# 01_MAIN.net
KiCad netlist of a schematic drawn in Altium Designer
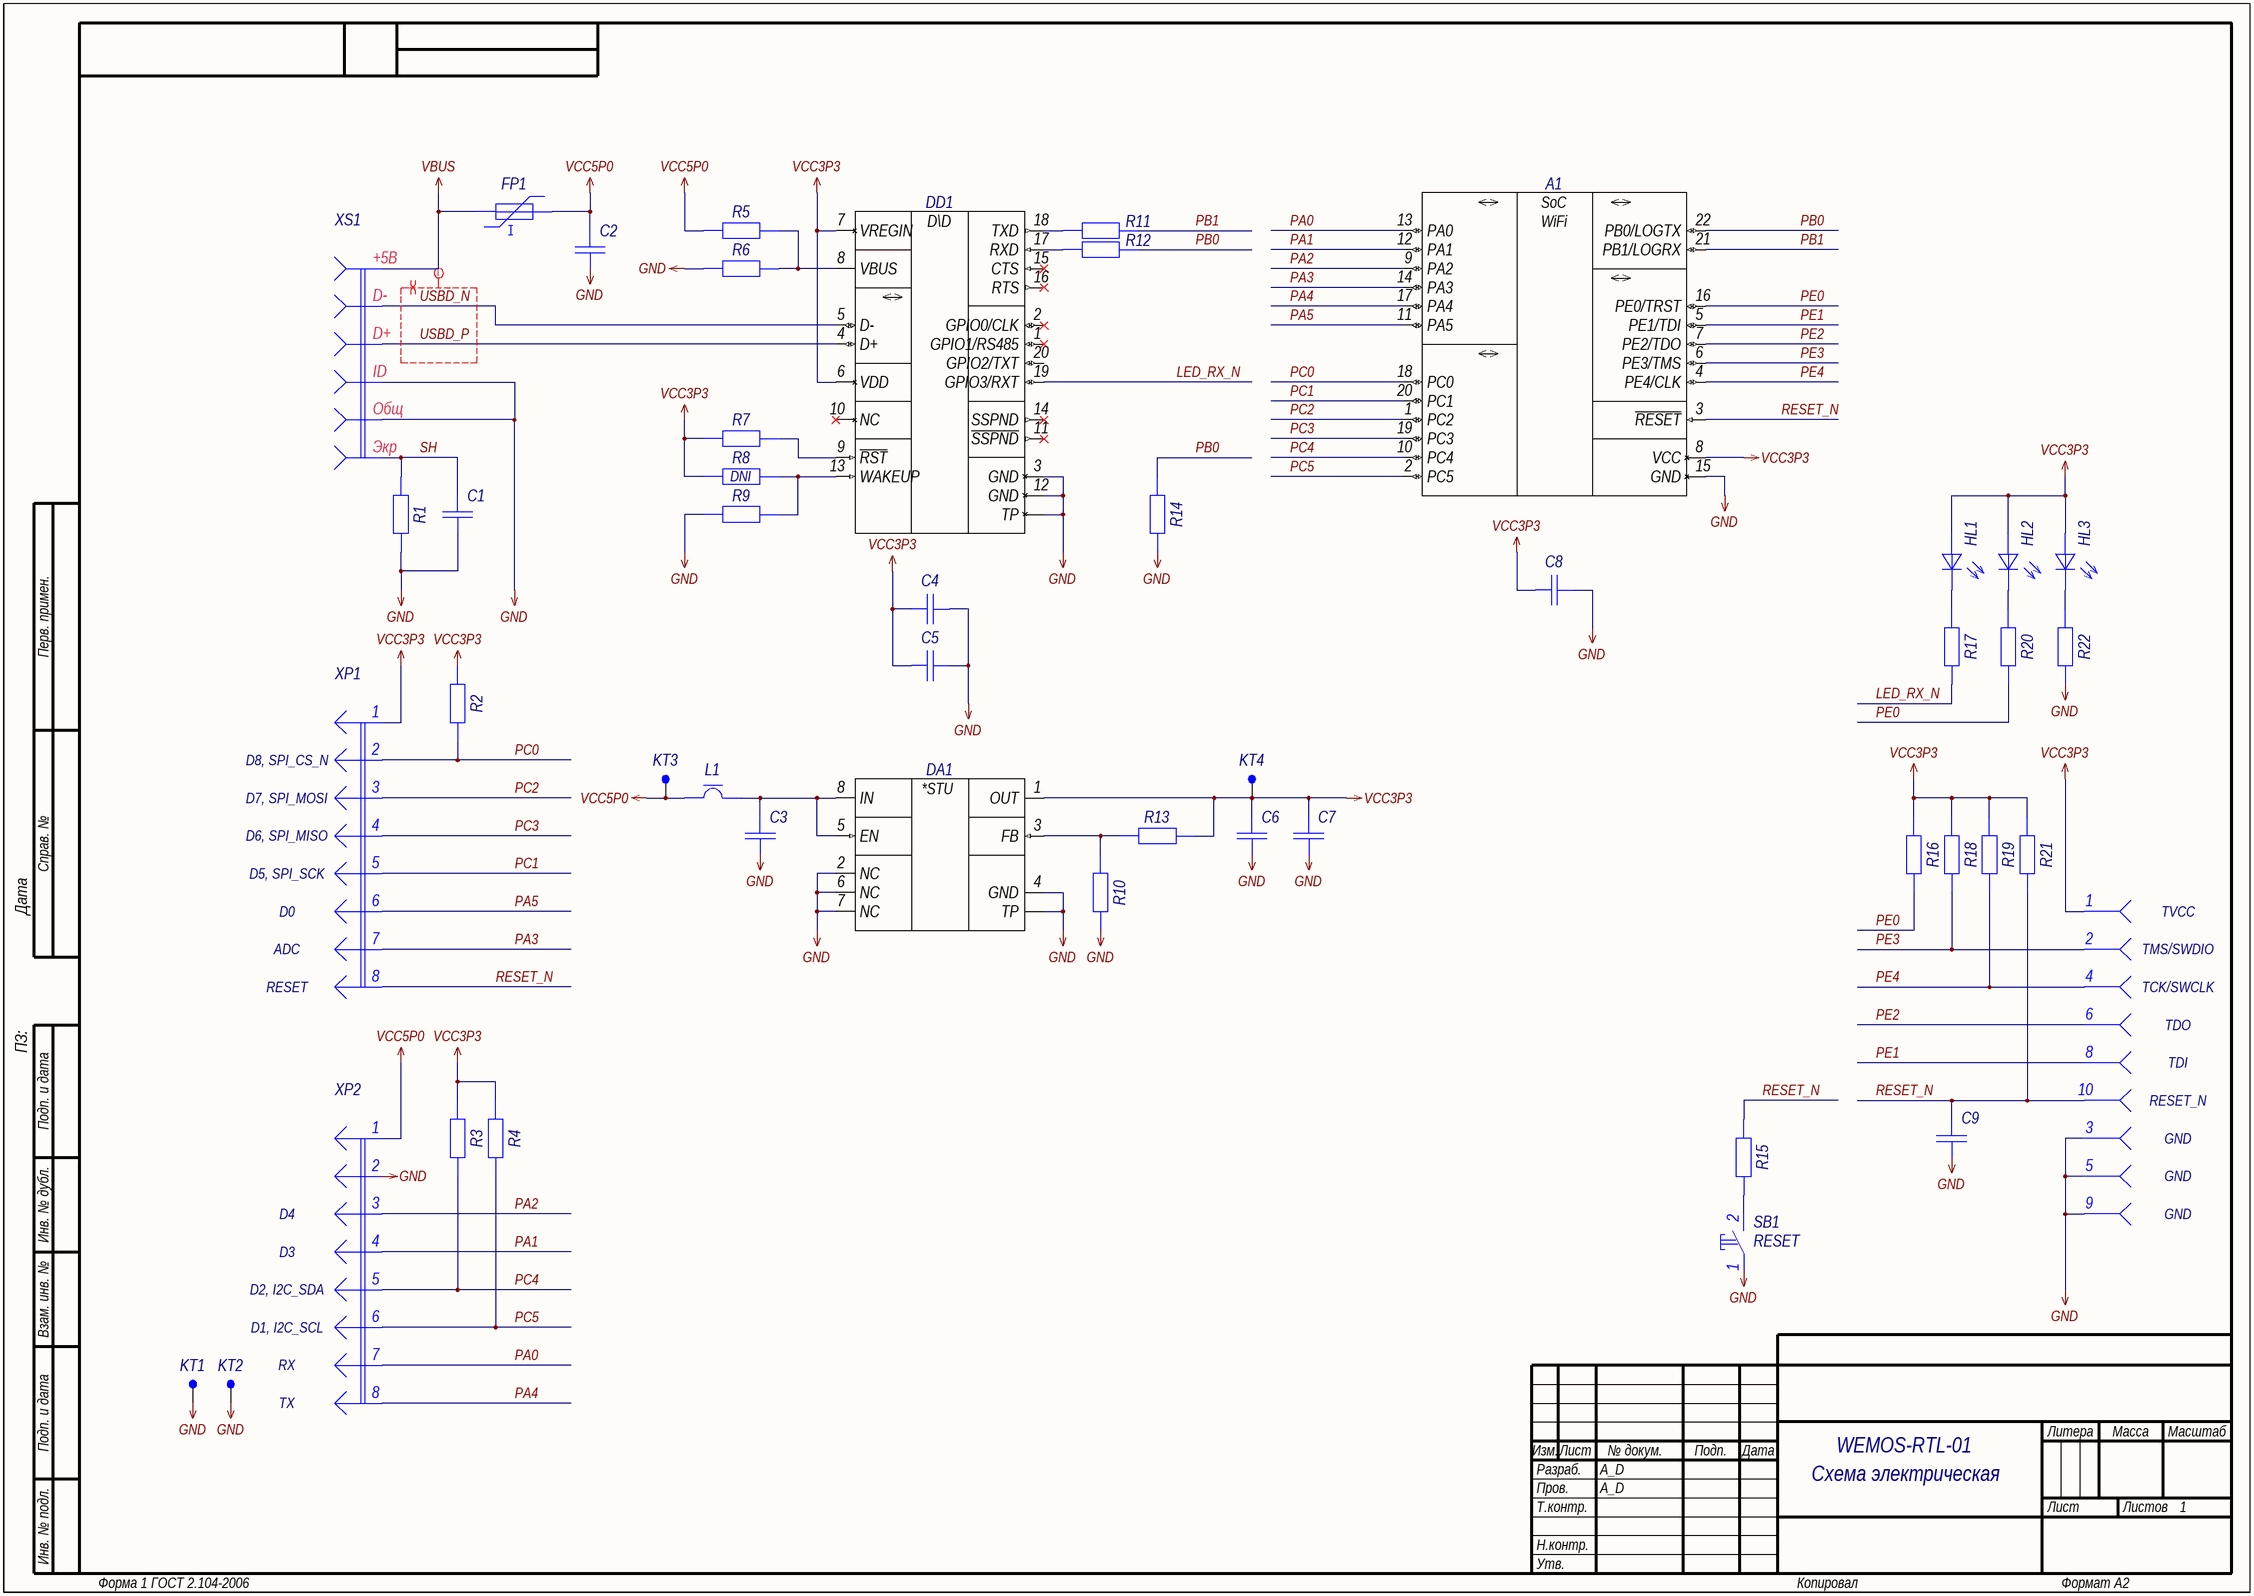
[diagram p0: 01_MAIN.SchDoc]

(export (version "E")
  (design (tool "Eeschema 10.0.6"))
  (components
    (comp (ref "A1")
      (value "RTL-00_01")
      (footprint "RTL-00")
      (fields
        (field (name "PART NUMBER") "RTL-00")
        (field (name "MANUFACTURER") "B&T")
        (field (name "PUBLISHER") "Andrew Danich")
      )
      (libsource (lib "ADLib") (part "RTL-00_01"))
    )
    (comp (ref "C1")
      (value "Capacitor")
      (footprint "C0603_L")
      (fields
        (field (name "PART NUMBER") "GRM188R72A104KA35D")
        (field (name "VOLTAGE") "100V")
        (field (name "TOLERANCE") "±10%")
        (field (name "PUBLISHER") "Andrew Danich")
      )
      (libsource (lib "ADLib") (part "Capacitor"))
    )
    (comp (ref "C2")
      (value "Capacitor")
      (footprint "C0603_L")
      (fields
        (field (name "PART NUMBER") "GRM188R60J106ME47D")
        (field (name "VOLTAGE") "6.3V")
        (field (name "TOLERANCE") "±20%")
        (field (name "PUBLISHER") "Andrew Danich")
      )
      (libsource (lib "ADLib") (part "Capacitor"))
    )
    (comp (ref "C3")
      (value "Capacitor")
      (footprint "C0402_L")
      (fields
        (field (name "PART NUMBER") "GRM155R60J475ME87D")
        (field (name "VOLTAGE") "6.3V")
        (field (name "TOLERANCE") "±20%")
        (field (name "PUBLISHER") "Andrew Danich")
      )
      (libsource (lib "ADLib") (part "Capacitor"))
    )
    (comp (ref "C4")
      (value "Capacitor")
      (footprint "C0402_L")
      (fields
        (field (name "PART NUMBER") "GRM155R60J475ME87D")
        (field (name "VOLTAGE") "6.3V")
        (field (name "TOLERANCE") "±20%")
        (field (name "PUBLISHER") "Andrew Danich")
      )
      (libsource (lib "ADLib") (part "Capacitor"))
    )
    (comp (ref "C5")
      (value "Capacitor")
      (footprint "C0402_L")
      (fields
        (field (name "PART NUMBER") "GCM155R71C104KA55D")
        (field (name "VOLTAGE") "16V")
        (field (name "TOLERANCE") "±10%")
        (field (name "PUBLISHER") "Andrew Danich")
      )
      (libsource (lib "ADLib") (part "Capacitor"))
    )
    (comp (ref "C6")
      (value "Capacitor")
      (footprint "C0402_L")
      (fields
        (field (name "PART NUMBER") "GRM155R60J475ME87D")
        (field (name "VOLTAGE") "6.3V")
        (field (name "TOLERANCE") "±20%")
        (field (name "PUBLISHER") "Andrew Danich")
      )
      (libsource (lib "ADLib") (part "Capacitor"))
    )
    (comp (ref "C7")
      (value "Capacitor")
      (footprint "C0402_L")
      (fields
        (field (name "PART NUMBER") "GRM155R60J475ME87D")
        (field (name "VOLTAGE") "6.3V")
        (field (name "TOLERANCE") "±20%")
        (field (name "PUBLISHER") "Andrew Danich")
      )
      (libsource (lib "ADLib") (part "Capacitor"))
    )
    (comp (ref "C8")
      (value "Capacitor")
      (footprint "C0402_L")
      (fields
        (field (name "PART NUMBER") "GRM155R60J475ME87D")
        (field (name "VOLTAGE") "6.3V")
        (field (name "TOLERANCE") "±20%")
        (field (name "PUBLISHER") "Andrew Danich")
      )
      (libsource (lib "ADLib") (part "Capacitor"))
    )
    (comp (ref "C9")
      (value "Capacitor")
      (footprint "C0402_L")
      (fields
        (field (name "PART NUMBER") "GCM155R71C104KA55D")
        (field (name "VOLTAGE") "16V")
        (field (name "TOLERANCE") "±10%")
        (field (name "PUBLISHER") "Andrew Danich")
      )
      (libsource (lib "ADLib") (part "Capacitor"))
    )
    (comp (ref "DA1")
      (value "TPS73701DRB")
      (footprint "VSON-8_065P300X300X100_N")
      (fields
        (field (name "PART NUMBER") "TPS73701DRBR")
        (field (name "MANUFACTURER") "Texas Instruments")
        (field (name "PUBLISHER") "Andrew Danich")
      )
      (libsource (lib "ADLib") (part "TPS73701DRB"))
    )
    (comp (ref "DD1")
      (value "CP2102N-xxx-GQFN20")
      (footprint "QFN-20_050P300X300X080_N")
      (fields
        (field (name "PART NUMBER") "CP2102N-A01-GQFN20")
        (field (name "MANUFACTURER") "Silicon Labs")
        (field (name "PUBLISHER") "Andrew Danich")
      )
      (libsource (lib "ADLib") (part "CP2102N-xxx-GQFN20"))
    )
    (comp (ref "FP1")
      (value "Fuse_PTC")
      (footprint "F0603_L_H075")
      (fields (field (name "PART NUMBER") "0603L100SLYR") (field (name "MANUFACTURER") "Littelfuse"))
      (libsource (lib "ADLib") (part "Fuse_PTC"))
    )
    (comp (ref "HL1")
      (value "RX")
      (footprint "LD0402_L")
      (fields
        (field (name "PART NUMBER") "KPHHS-1005SURCK")
        (field (name "MANUFACTURER") "Kingbright")
        (field (name "PUBLISHER") "Andrew Danich")
      )
      (libsource (lib "ADLib") (part "Led-1"))
    )
    (comp (ref "HL2")
      (value "USER")
      (footprint "LD0402_L")
      (fields
        (field (name "PART NUMBER") "KPHHS-1005QBC-D-V")
        (field (name "MANUFACTURER") "Kingbright")
        (field (name "PUBLISHER") "Andrew Danich")
      )
      (libsource (lib "ADLib") (part "Led-1"))
    )
    (comp (ref "HL3")
      (value "POWER")
      (footprint "LD0402_L")
      (fields
        (field (name "PART NUMBER") "KPHHS-1005CGCK")
        (field (name "MANUFACTURER") "Kingbright")
        (field (name "PUBLISHER") "Andrew Danich")
      )
      (libsource (lib "ADLib") (part "Led-1"))
    )
    (comp (ref "KT1")
      (value "GND")
      (footprint "TP-SMT-R-0.8mm")
      (fields (field (name "PART NUMBER") "TestPoint-SMT-GND") (field (name "PUBLISHER") "Andrew Danich"))
      (libsource (lib "ADLib") (part "TP-S-1"))
    )
    (comp (ref "KT2")
      (value "GND")
      (footprint "TP-SMT-R-0.8mm")
      (fields (field (name "PART NUMBER") "TestPoint-SMT-GND") (field (name "PUBLISHER") "Andrew Danich"))
      (libsource (lib "ADLib") (part "TP-S-1"))
    )
    (comp (ref "KT3")
      (value "5P0")
      (footprint "TP-SMT-C-0.5mm")
      (fields (field (name "PART NUMBER") "TestPoint-SMT") (field (name "PUBLISHER") "Andrew Danich"))
      (libsource (lib "ADLib") (part "TP-S-1"))
    )
    (comp (ref "KT4")
      (value "3P3")
      (footprint "TP-SMT-C-0.5mm")
      (fields (field (name "PART NUMBER") "TestPoint-SMT") (field (name "PUBLISHER") "Andrew Danich"))
      (libsource (lib "ADLib") (part "TP-S-1"))
    )
    (comp (ref "L1")
      (value "FerriteBead")
      (footprint "L0402_L")
      (fields
        (field (name "PART NUMBER") "BLM15PD121SN1D")
        (field (name "TOLERANCE") "±25%")
        (field (name "MANUFACTURER") "Murata")
        (field (name "PUBLISHER") "Andrew Danich")
      )
      (libsource (lib "ADLib") (part "FerriteBead"))
    )
    (comp (ref "R1")
      (value "Resistor")
      (footprint "R0603_L")
      (fields
        (field (name "PART NUMBER") "RC0603JR-070R")
        (field (name "TOLERANCE") "±5%")
        (field (name "MANUFACTURER") "Yageo")
        (field (name "PUBLISHER") "Andrew Danich")
      )
      (libsource (lib "ADLib") (part "Resistor"))
    )
    (comp (ref "R2")
      (value "Resistor")
      (footprint "R0402_L")
      (fields
        (field (name "PART NUMBER") "RC0402JR-0710KL")
        (field (name "TOLERANCE") "±5%")
        (field (name "MANUFACTURER") "Yageo")
        (field (name "PUBLISHER") "Andrew Danich")
      )
      (libsource (lib "ADLib") (part "Resistor"))
    )
    (comp (ref "R3")
      (value "Resistor")
      (footprint "R0402_L")
      (fields
        (field (name "PART NUMBER") "RC0402JR-0710KL")
        (field (name "TOLERANCE") "±5%")
        (field (name "MANUFACTURER") "Yageo")
        (field (name "PUBLISHER") "Andrew Danich")
      )
      (libsource (lib "ADLib") (part "Resistor"))
    )
    (comp (ref "R4")
      (value "Resistor")
      (footprint "R0402_L")
      (fields
        (field (name "PART NUMBER") "RC0402JR-0710KL")
        (field (name "TOLERANCE") "±5%")
        (field (name "MANUFACTURER") "Yageo")
        (field (name "PUBLISHER") "Andrew Danich")
      )
      (libsource (lib "ADLib") (part "Resistor"))
    )
    (comp (ref "R5")
      (value "Resistor")
      (footprint "R0402_L")
      (fields
        (field (name "PART NUMBER") "RC0402FR-0722K1L")
        (field (name "TOLERANCE") "±1%")
        (field (name "MANUFACTURER") "Yageo")
        (field (name "PUBLISHER") "Andrew Danich")
      )
      (libsource (lib "ADLib") (part "Resistor"))
    )
    (comp (ref "R6")
      (value "Resistor")
      (footprint "R0402_L")
      (fields
        (field (name "PART NUMBER") "RC0402FR-0747KL")
        (field (name "TOLERANCE") "±1%")
        (field (name "MANUFACTURER") "Yageo")
        (field (name "PUBLISHER") "Andrew Danich")
      )
      (libsource (lib "ADLib") (part "Resistor"))
    )
    (comp (ref "R7")
      (value "Resistor")
      (footprint "R0402_L")
      (fields
        (field (name "PART NUMBER") "RC0402JR-0710KL")
        (field (name "TOLERANCE") "±5%")
        (field (name "MANUFACTURER") "Yageo")
        (field (name "PUBLISHER") "Andrew Danich")
      )
      (libsource (lib "ADLib") (part "Resistor"))
    )
    (comp (ref "R8")
      (value "Resistor")
      (footprint "R0402_L")
      (fields
        (field (name "PART NUMBER") "RC0402JR-0710KL")
        (field (name "TOLERANCE") "±5%")
        (field (name "MANUFACTURER") "Yageo")
        (field (name "PUBLISHER") "Andrew Danich")
      )
      (libsource (lib "ADLib") (part "Resistor"))
    )
    (comp (ref "R9")
      (value "Resistor")
      (footprint "R0402_L")
      (fields
        (field (name "PART NUMBER") "RC0402JR-070RL")
        (field (name "TOLERANCE") "±5%")
        (field (name "MANUFACTURER") "Yageo")
        (field (name "PUBLISHER") "Andrew Danich")
      )
      (libsource (lib "ADLib") (part "Resistor"))
    )
    (comp (ref "R10")
      (value "Resistor")
      (footprint "R0402_L")
      (fields
        (field (name "PART NUMBER") "RC0402FR-0712KL")
        (field (name "TOLERANCE") "±1%")
        (field (name "MANUFACTURER") "Yageo")
        (field (name "PUBLISHER") "Andrew Danich")
      )
      (libsource (lib "ADLib") (part "Resistor"))
    )
    (comp (ref "R11")
      (value "Resistor")
      (footprint "R0402_L")
      (fields
        (field (name "PART NUMBER") "RC0402JR-070RL")
        (field (name "TOLERANCE") "±5%")
        (field (name "MANUFACTURER") "Yageo")
        (field (name "PUBLISHER") "Andrew Danich")
      )
      (libsource (lib "ADLib") (part "Resistor"))
    )
    (comp (ref "R12")
      (value "Resistor")
      (footprint "R0402_L")
      (fields
        (field (name "PART NUMBER") "RC0402JR-070RL")
        (field (name "TOLERANCE") "±5%")
        (field (name "MANUFACTURER") "Yageo")
        (field (name "PUBLISHER") "Andrew Danich")
      )
      (libsource (lib "ADLib") (part "Resistor"))
    )
    (comp (ref "R13")
      (value "Resistor")
      (footprint "R0402_L")
      (fields
        (field (name "PART NUMBER") "RC0402FR-0722K1L")
        (field (name "TOLERANCE") "±1%")
        (field (name "MANUFACTURER") "Yageo")
        (field (name "PUBLISHER") "Andrew Danich")
      )
      (libsource (lib "ADLib") (part "Resistor"))
    )
    (comp (ref "R14")
      (value "Resistor")
      (footprint "R0402_L")
      (fields
        (field (name "PART NUMBER") "RC0402JR-0710KL")
        (field (name "TOLERANCE") "±5%")
        (field (name "MANUFACTURER") "Yageo")
        (field (name "PUBLISHER") "Andrew Danich")
      )
      (libsource (lib "ADLib") (part "Resistor"))
    )
    (comp (ref "R15")
      (value "Resistor")
      (footprint "R0402_L")
      (fields
        (field (name "PART NUMBER") "RC0402JR-0720RL")
        (field (name "TOLERANCE") "±5%")
        (field (name "MANUFACTURER") "Yageo")
        (field (name "PUBLISHER") "Andrew Danich")
      )
      (libsource (lib "ADLib") (part "Resistor"))
    )
    (comp (ref "R16")
      (value "Resistor")
      (footprint "R0402_L")
      (fields
        (field (name "PART NUMBER") "RC0402JR-0710KL")
        (field (name "TOLERANCE") "±5%")
        (field (name "MANUFACTURER") "Yageo")
        (field (name "PUBLISHER") "Andrew Danich")
      )
      (libsource (lib "ADLib") (part "Resistor"))
    )
    (comp (ref "R17")
      (value "Resistor")
      (footprint "R0402_L")
      (fields
        (field (name "PART NUMBER") "RC0402JR-071KL")
        (field (name "TOLERANCE") "±5%")
        (field (name "MANUFACTURER") "Yageo")
        (field (name "PUBLISHER") "Andrew Danich")
      )
      (libsource (lib "ADLib") (part "Resistor"))
    )
    (comp (ref "R18")
      (value "Resistor")
      (footprint "R0402_L")
      (fields
        (field (name "PART NUMBER") "RC0402JR-0710KL")
        (field (name "TOLERANCE") "±5%")
        (field (name "MANUFACTURER") "Yageo")
        (field (name "PUBLISHER") "Andrew Danich")
      )
      (libsource (lib "ADLib") (part "Resistor"))
    )
    (comp (ref "R19")
      (value "Resistor")
      (footprint "R0402_L")
      (fields
        (field (name "PART NUMBER") "RC0402JR-0710KL")
        (field (name "TOLERANCE") "±5%")
        (field (name "MANUFACTURER") "Yageo")
        (field (name "PUBLISHER") "Andrew Danich")
      )
      (libsource (lib "ADLib") (part "Resistor"))
    )
    (comp (ref "R20")
      (value "Resistor")
      (footprint "R0402_L")
      (fields
        (field (name "PART NUMBER") "RC0402JR-071KL")
        (field (name "TOLERANCE") "±5%")
        (field (name "MANUFACTURER") "Yageo")
        (field (name "PUBLISHER") "Andrew Danich")
      )
      (libsource (lib "ADLib") (part "Resistor"))
    )
    (comp (ref "R21")
      (value "Resistor")
      (footprint "R0402_L")
      (fields
        (field (name "PART NUMBER") "RC0402JR-0710KL")
        (field (name "TOLERANCE") "±5%")
        (field (name "MANUFACTURER") "Yageo")
        (field (name "PUBLISHER") "Andrew Danich")
      )
      (libsource (lib "ADLib") (part "Resistor"))
    )
    (comp (ref "R22")
      (value "Resistor")
      (footprint "R0402_L")
      (fields
        (field (name "PART NUMBER") "RC0402JR-071KL")
        (field (name "TOLERANCE") "±5%")
        (field (name "MANUFACTURER") "Yageo")
        (field (name "PUBLISHER") "Andrew Danich")
      )
      (libsource (lib "ADLib") (part "Resistor"))
    )
    (comp (ref "SB1")
      (value "RESET")
      (footprint "1TS003B-Series")
      (fields
        (field (name "PART NUMBER") "1TS003B-1600-3500A-CT")
        (field (name "MANUFACTURER") "Hongyuan Precision")
        (field (name "PUBLISHER") "Andrew Danich")
      )
      (libsource (lib "ADLib") (part "BT-01x-01p"))
    )
    (comp (ref "XP1")
      (value "Text")
      (footprint "PLS-8")
      (fields (field (name "PART NUMBER") "PLS-8") (field (name "PUBLISHER") "Andrew Danich"))
      (libsource (lib "ADLib") (part "Con-8-M"))
    )
    (comp (ref "XP2")
      (value "Text")
      (footprint "PLS-8")
      (fields (field (name "PART NUMBER") "PLS-8") (field (name "PUBLISHER") "Andrew Danich"))
      (libsource (lib "ADLib") (part "Con-8-M"))
    )
    (comp (ref "XS1")
      (value "Text")
      (footprint "1981568-1")
      (fields
        (field (name "PART NUMBER") "1981568-1")
        (field (name "MANUFACTURER") "TE Connectivity")
        (field (name "PUBLISHER") "Andrew Danich")
      )
      (libsource (lib "ADLib") (part "Con-6-F-USB"))
    )
    (comp (ref "XS2")
      (value "JTAG")
      (footprint "XF2M-1015-1A")
      (fields
        (field (name "PART NUMBER") "XF2M-1015-1A")
        (field (name "MANUFACTURER") "Omron Electronics")
        (field (name "PUBLISHER") "Viktor Klishin")
      )
      (libsource (lib "ADLib") (part "Con-10-F_S"))
    )
  )
  (nets
    (net (code "1") (name "/LED_RX_N") (class "Default")
      (node (ref "DD1") (pin "19") (pinfunction "GPIO3/RXT_19") (pintype "bidirectional"))
      (node (ref "R17") (pin "1") (pinfunction "1_1") (pintype "passive"))
    )
    (net (code "2") (name "/PA0") (class "Default")
      (node (ref "A1") (pin "13") (pinfunction "PA0_13") (pintype "bidirectional"))
      (node (ref "XP2") (pin "7") (pintype "passive"))
    )
    (net (code "3") (name "/PA1") (class "Default")
      (node (ref "A1") (pin "12") (pinfunction "PA1_12") (pintype "bidirectional"))
      (node (ref "XP2") (pin "4") (pintype "passive"))
    )
    (net (code "4") (name "/PA2") (class "Default")
      (node (ref "A1") (pin "9") (pinfunction "PA2_9") (pintype "bidirectional"))
      (node (ref "XP2") (pin "3") (pintype "passive"))
    )
    (net (code "5") (name "/PA3") (class "Default")
      (node (ref "A1") (pin "14") (pinfunction "PA3_14") (pintype "bidirectional"))
      (node (ref "XP1") (pin "7") (pintype "passive"))
    )
    (net (code "6") (name "/PA4") (class "Default")
      (node (ref "A1") (pin "17") (pinfunction "PA4_17") (pintype "bidirectional"))
      (node (ref "XP2") (pin "8") (pintype "passive"))
    )
    (net (code "7") (name "/PA5") (class "Default")
      (node (ref "A1") (pin "11") (pinfunction "PA5_11") (pintype "bidirectional"))
      (node (ref "XP1") (pin "6") (pintype "passive"))
    )
    (net (code "8") (name "/PB0") (class "Default")
      (node (ref "A1") (pin "22") (pinfunction "PB0/LOGTX_22") (pintype "bidirectional"))
      (node (ref "R12") (pin "2") (pinfunction "2_2") (pintype "passive"))
      (node (ref "R14") (pin "2") (pinfunction "2_2") (pintype "passive"))
    )
    (net (code "9") (name "/PB1") (class "Default")
      (node (ref "A1") (pin "21") (pinfunction "PB1/LOGRX_21") (pintype "bidirectional"))
      (node (ref "R11") (pin "2") (pinfunction "2_2") (pintype "passive"))
    )
    (net (code "10") (name "/PC0") (class "Default")
      (node (ref "A1") (pin "18") (pinfunction "PC0_18") (pintype "bidirectional"))
      (node (ref "R2") (pin "2") (pinfunction "2_2") (pintype "passive"))
      (node (ref "XP1") (pin "2") (pintype "passive"))
    )
    (net (code "11") (name "/PC1") (class "Default")
      (node (ref "A1") (pin "20") (pinfunction "PC1_20") (pintype "bidirectional"))
      (node (ref "XP1") (pin "5") (pintype "passive"))
    )
    (net (code "12") (name "/PC2") (class "Default")
      (node (ref "A1") (pin "1") (pinfunction "PC2_1") (pintype "bidirectional"))
      (node (ref "XP1") (pin "3") (pintype "passive"))
    )
    (net (code "13") (name "/PC3") (class "Default")
      (node (ref "A1") (pin "19") (pinfunction "PC3_19") (pintype "bidirectional"))
      (node (ref "XP1") (pin "4") (pintype "passive"))
    )
    (net (code "14") (name "/PC4") (class "Default")
      (node (ref "A1") (pin "10") (pinfunction "PC4_10") (pintype "bidirectional"))
      (node (ref "R3") (pin "2") (pinfunction "2_2") (pintype "passive"))
      (node (ref "XP2") (pin "5") (pintype "passive"))
    )
    (net (code "15") (name "/PC5") (class "Default")
      (node (ref "A1") (pin "2") (pinfunction "PC5_2") (pintype "bidirectional"))
      (node (ref "R4") (pin "2") (pinfunction "2_2") (pintype "passive"))
      (node (ref "XP2") (pin "6") (pintype "passive"))
    )
    (net (code "16") (name "/PE0") (class "Default")
      (node (ref "A1") (pin "16") (pinfunction "PE0/TRST_16") (pintype "bidirectional"))
      (node (ref "R16") (pin "2") (pinfunction "2_2") (pintype "passive"))
      (node (ref "R20") (pin "1") (pinfunction "1_1") (pintype "passive"))
    )
    (net (code "17") (name "/PE1") (class "Default")
      (node (ref "A1") (pin "5") (pinfunction "PE1/TDI_5") (pintype "bidirectional"))
      (node (ref "XS2") (pin "8") (pintype "passive"))
    )
    (net (code "18") (name "/PE2") (class "Default")
      (node (ref "A1") (pin "7") (pinfunction "PE2/TDO_7") (pintype "bidirectional"))
      (node (ref "XS2") (pin "6") (pintype "passive"))
    )
    (net (code "19") (name "/PE3") (class "Default")
      (node (ref "A1") (pin "6") (pinfunction "PE3/TMS_6") (pintype "bidirectional"))
      (node (ref "R18") (pin "2") (pinfunction "2_2") (pintype "passive"))
      (node (ref "XS2") (pin "2") (pintype "passive"))
    )
    (net (code "20") (name "/PE4") (class "Default")
      (node (ref "A1") (pin "4") (pinfunction "PE4/CLK_4") (pintype "bidirectional"))
      (node (ref "R19") (pin "2") (pinfunction "2_2") (pintype "passive"))
      (node (ref "XS2") (pin "4") (pintype "passive"))
    )
    (net (code "21") (name "/RESET_N") (class "Default")
      (node (ref "A1") (pin "3") (pinfunction "~{RESET}_3") (pintype "input"))
      (node (ref "C9") (pin "2") (pinfunction "2_2") (pintype "passive"))
      (node (ref "R15") (pin "2") (pinfunction "2_2") (pintype "passive"))
      (node (ref "R21") (pin "2") (pinfunction "2_2") (pintype "passive"))
      (node (ref "XP1") (pin "8") (pintype "passive"))
      (node (ref "XS2") (pin "10") (pintype "passive"))
    )
    (net (code "22") (name "/SH") (class "Default")
      (node (ref "C1") (pin "2") (pinfunction "2_2") (pintype "passive"))
      (node (ref "R1") (pin "2") (pinfunction "2_2") (pintype "passive"))
      (node (ref "XS1") (pin "6") (pintype "passive"))
    )
    (net (code "23") (name "/USBD_N") (class "Default")
      (node (ref "DD1") (pin "5") (pinfunction "D-_5") (pintype "bidirectional"))
      (node (ref "XS1") (pin "2") (pintype "passive"))
    )
    (net (code "24") (name "/USBD_P") (class "Default")
      (node (ref "DD1") (pin "4") (pinfunction "D+_4") (pintype "bidirectional"))
      (node (ref "XS1") (pin "3") (pintype "passive"))
    )
    (net (code "25") (name "GND") (class "Default")
      (node (ref "A1") (pin "15") (pinfunction "GND_15") (pintype "power_in"))
      (node (ref "C1") (pin "1") (pinfunction "1_1") (pintype "passive"))
      (node (ref "C2") (pin "1") (pinfunction "1_1") (pintype "passive"))
      (node (ref "C3") (pin "1") (pinfunction "1_1") (pintype "passive"))
      (node (ref "C4") (pin "1") (pinfunction "1_1") (pintype "passive"))
      (node (ref "C5") (pin "1") (pinfunction "1_1") (pintype "passive"))
      (node (ref "C6") (pin "1") (pinfunction "1_1") (pintype "passive"))
      (node (ref "C7") (pin "1") (pinfunction "1_1") (pintype "passive"))
      (node (ref "C8") (pin "1") (pinfunction "1_1") (pintype "passive"))
      (node (ref "C9") (pin "1") (pinfunction "1_1") (pintype "passive"))
      (node (ref "DA1") (pin "2") (pinfunction "NC_2") (pintype "passive"))
      (node (ref "DA1") (pin "4") (pinfunction "GND_4") (pintype "power_in"))
      (node (ref "DA1") (pin "6") (pinfunction "NC_6") (pintype "passive"))
      (node (ref "DA1") (pin "7") (pinfunction "NC_7") (pintype "passive"))
      (node (ref "DA1") (pin "TP") (pinfunction "TP_TP") (pintype "passive"))
      (node (ref "DD1") (pin "12") (pinfunction "GND_12") (pintype "power_in"))
      (node (ref "DD1") (pin "3") (pinfunction "GND_3") (pintype "power_in"))
      (node (ref "DD1") (pin "TP") (pinfunction "TP_TP") (pintype "power_in"))
      (node (ref "KT1") (pin "1") (pinfunction "1_1") (pintype "passive"))
      (node (ref "KT2") (pin "1") (pinfunction "1_1") (pintype "passive"))
      (node (ref "R1") (pin "1") (pinfunction "1_1") (pintype "passive"))
      (node (ref "R10") (pin "1") (pinfunction "1_1") (pintype "passive"))
      (node (ref "R14") (pin "1") (pinfunction "1_1") (pintype "passive"))
      (node (ref "R22") (pin "1") (pinfunction "1_1") (pintype "passive"))
      (node (ref "R6") (pin "1") (pinfunction "1_1") (pintype "passive"))
      (node (ref "R9") (pin "1") (pinfunction "1_1") (pintype "passive"))
      (node (ref "SB1") (pin "1") (pintype "passive"))
      (node (ref "XP2") (pin "2") (pintype "passive"))
      (node (ref "XS1") (pin "4") (pintype "passive"))
      (node (ref "XS1") (pin "5") (pintype "passive"))
      (node (ref "XS2") (pin "3") (pintype "passive"))
      (node (ref "XS2") (pin "5") (pintype "passive"))
      (node (ref "XS2") (pin "9") (pintype "passive"))
    )
    (net (code "26") (name "Net-(DA1-EN)") (class "Default")
      (node (ref "C3") (pin "2") (pinfunction "2_2") (pintype "passive"))
      (node (ref "DA1") (pin "5") (pinfunction "EN_5") (pintype "input"))
      (node (ref "DA1") (pin "8") (pinfunction "IN_8") (pintype "power_in"))
      (node (ref "L1") (pin "2") (pinfunction "2_2") (pintype "passive"))
    )
    (net (code "27") (name "Net-(DA1-FB)") (class "Default")
      (node (ref "DA1") (pin "3") (pinfunction "FB_3") (pintype "input"))
      (node (ref "R10") (pin "2") (pinfunction "2_2") (pintype "passive"))
      (node (ref "R13") (pin "1") (pinfunction "1_1") (pintype "passive"))
    )
    (net (code "28") (name "Net-(DD1-RXD)") (class "Default")
      (node (ref "DD1") (pin "17") (pinfunction "RXD_17") (pintype "input"))
      (node (ref "R12") (pin "1") (pinfunction "1_1") (pintype "passive"))
    )
    (net (code "29") (name "Net-(DD1-TXD)") (class "Default")
      (node (ref "DD1") (pin "18") (pinfunction "TXD_18") (pintype "output"))
      (node (ref "R11") (pin "1") (pinfunction "1_1") (pintype "passive"))
    )
    (net (code "30") (name "Net-(DD1-VBUS)") (class "Default")
      (node (ref "DD1") (pin "8") (pinfunction "VBUS_8") (pintype "power_in"))
      (node (ref "R5") (pin "2") (pinfunction "2_2") (pintype "passive"))
      (node (ref "R6") (pin "2") (pinfunction "2_2") (pintype "passive"))
    )
    (net (code "31") (name "Net-(DD1-WAKEUP)") (class "Default")
      (node (ref "DD1") (pin "13") (pinfunction "WAKEUP_13") (pintype "input"))
      (node (ref "R8") (pin "1") (pinfunction "1_1") (pintype "passive"))
      (node (ref "R9") (pin "2") (pinfunction "2_2") (pintype "passive"))
    )
    (net (code "32") (name "Net-(DD1-~{RST})") (class "Default")
      (node (ref "DD1") (pin "9") (pinfunction "~{RST}_9") (pintype "input"))
      (node (ref "R7") (pin "1") (pinfunction "1_1") (pintype "passive"))
    )
    (net (code "33") (name "Net-(HL1-К)") (class "Default")
      (node (ref "HL1") (pin "2") (pinfunction "К_2") (pintype "passive"))
      (node (ref "R17") (pin "2") (pinfunction "2_2") (pintype "passive"))
    )
    (net (code "34") (name "Net-(HL2-К)") (class "Default")
      (node (ref "HL2") (pin "2") (pinfunction "К_2") (pintype "passive"))
      (node (ref "R20") (pin "2") (pinfunction "2_2") (pintype "passive"))
    )
    (net (code "35") (name "Net-(HL3-К)") (class "Default")
      (node (ref "HL3") (pin "2") (pinfunction "К_2") (pintype "passive"))
      (node (ref "R22") (pin "2") (pinfunction "2_2") (pintype "passive"))
    )
    (net (code "36") (name "Net-(R15-Pad1)") (class "Default")
      (node (ref "R15") (pin "1") (pinfunction "1_1") (pintype "passive"))
      (node (ref "SB1") (pin "2") (pintype "passive"))
    )
    (net (code "37") (name "VBUS") (class "Default")
      (node (ref "FP1") (pin "1") (pinfunction "1_1") (pintype "passive"))
      (node (ref "XS1") (pin "1") (pintype "passive"))
    )
    (net (code "38") (name "VCC3P3") (class "Default")
      (node (ref "A1") (pin "8") (pinfunction "VCC_8") (pintype "power_in"))
      (node (ref "C4") (pin "2") (pinfunction "2_2") (pintype "passive"))
      (node (ref "C5") (pin "2") (pinfunction "2_2") (pintype "passive"))
      (node (ref "C6") (pin "2") (pinfunction "2_2") (pintype "passive"))
      (node (ref "C7") (pin "2") (pinfunction "2_2") (pintype "passive"))
      (node (ref "C8") (pin "2") (pinfunction "2_2") (pintype "passive"))
      (node (ref "DA1") (pin "1") (pinfunction "OUT_1") (pintype "power_in"))
      (node (ref "DD1") (pin "6") (pinfunction "VDD_6") (pintype "power_in"))
      (node (ref "DD1") (pin "7") (pinfunction "VREGIN_7") (pintype "power_in"))
      (node (ref "HL1") (pin "1") (pinfunction "А_1") (pintype "passive"))
      (node (ref "HL2") (pin "1") (pinfunction "А_1") (pintype "passive"))
      (node (ref "HL3") (pin "1") (pinfunction "А_1") (pintype "passive"))
      (node (ref "KT4") (pin "1") (pinfunction "1_1") (pintype "passive"))
      (node (ref "R13") (pin "2") (pinfunction "2_2") (pintype "passive"))
      (node (ref "R16") (pin "1") (pinfunction "1_1") (pintype "passive"))
      (node (ref "R18") (pin "1") (pinfunction "1_1") (pintype "passive"))
      (node (ref "R19") (pin "1") (pinfunction "1_1") (pintype "passive"))
      (node (ref "R2") (pin "1") (pinfunction "1_1") (pintype "passive"))
      (node (ref "R21") (pin "1") (pinfunction "1_1") (pintype "passive"))
      (node (ref "R3") (pin "1") (pinfunction "1_1") (pintype "passive"))
      (node (ref "R4") (pin "1") (pinfunction "1_1") (pintype "passive"))
      (node (ref "R7") (pin "2") (pinfunction "2_2") (pintype "passive"))
      (node (ref "R8") (pin "2") (pinfunction "2_2") (pintype "passive"))
      (node (ref "XP1") (pin "1") (pintype "passive"))
      (node (ref "XS2") (pin "1") (pintype "passive"))
    )
    (net (code "39") (name "VCC5P0") (class "Default")
      (node (ref "C2") (pin "2") (pinfunction "2_2") (pintype "passive"))
      (node (ref "FP1") (pin "2") (pinfunction "2_2") (pintype "passive"))
      (node (ref "KT3") (pin "1") (pinfunction "1_1") (pintype "passive"))
      (node (ref "L1") (pin "1") (pinfunction "1_1") (pintype "passive"))
      (node (ref "R5") (pin "1") (pinfunction "1_1") (pintype "passive"))
      (node (ref "XP2") (pin "1") (pintype "passive"))
    )
    (net (code "40") (name "unconnected-(DD1-CTS-Pad15)") (class "Default")
      (node (ref "DD1") (pin "15") (pinfunction "CTS_15") (pintype "input+no_connect"))
    )
    (net (code "41") (name "unconnected-(DD1-GPIO0{slash}CLK-Pad2)") (class "Default")
      (node (ref "DD1") (pin "2") (pinfunction "GPIO0/CLK_2") (pintype "bidirectional+no_connect"))
    )
    (net (code "42") (name "unconnected-(DD1-GPIO1{slash}RS485-Pad1)") (class "Default")
      (node (ref "DD1") (pin "1") (pinfunction "GPIO1/RS485_1") (pintype "bidirectional+no_connect"))
    )
    (net (code "43") (name "unconnected-(DD1-GPIO2{slash}TXT-Pad20)") (class "Default")
      (node (ref "DD1") (pin "20") (pinfunction "GPIO2/TXT_20") (pintype "bidirectional"))
    )
    (net (code "44") (name "unconnected-(DD1-NC-Pad10)") (class "Default")
      (node (ref "DD1") (pin "10") (pinfunction "NC_10") (pintype "passive+no_connect"))
    )
    (net (code "45") (name "unconnected-(DD1-RTS-Pad16)") (class "Default")
      (node (ref "DD1") (pin "16") (pinfunction "RTS_16") (pintype "output+no_connect"))
    )
    (net (code "46") (name "unconnected-(DD1-SSPND-Pad14)") (class "Default")
      (node (ref "DD1") (pin "14") (pinfunction "SSPND_14") (pintype "output+no_connect"))
    )
    (net (code "47") (name "unconnected-(DD1-~{SSPND}-Pad11)") (class "Default")
      (node (ref "DD1") (pin "11") (pinfunction "~{SSPND}_11") (pintype "output+no_connect"))
    )
  )
)
